# BMS_Segment.net
KiCad netlist of a schematic drawn in EAGLE
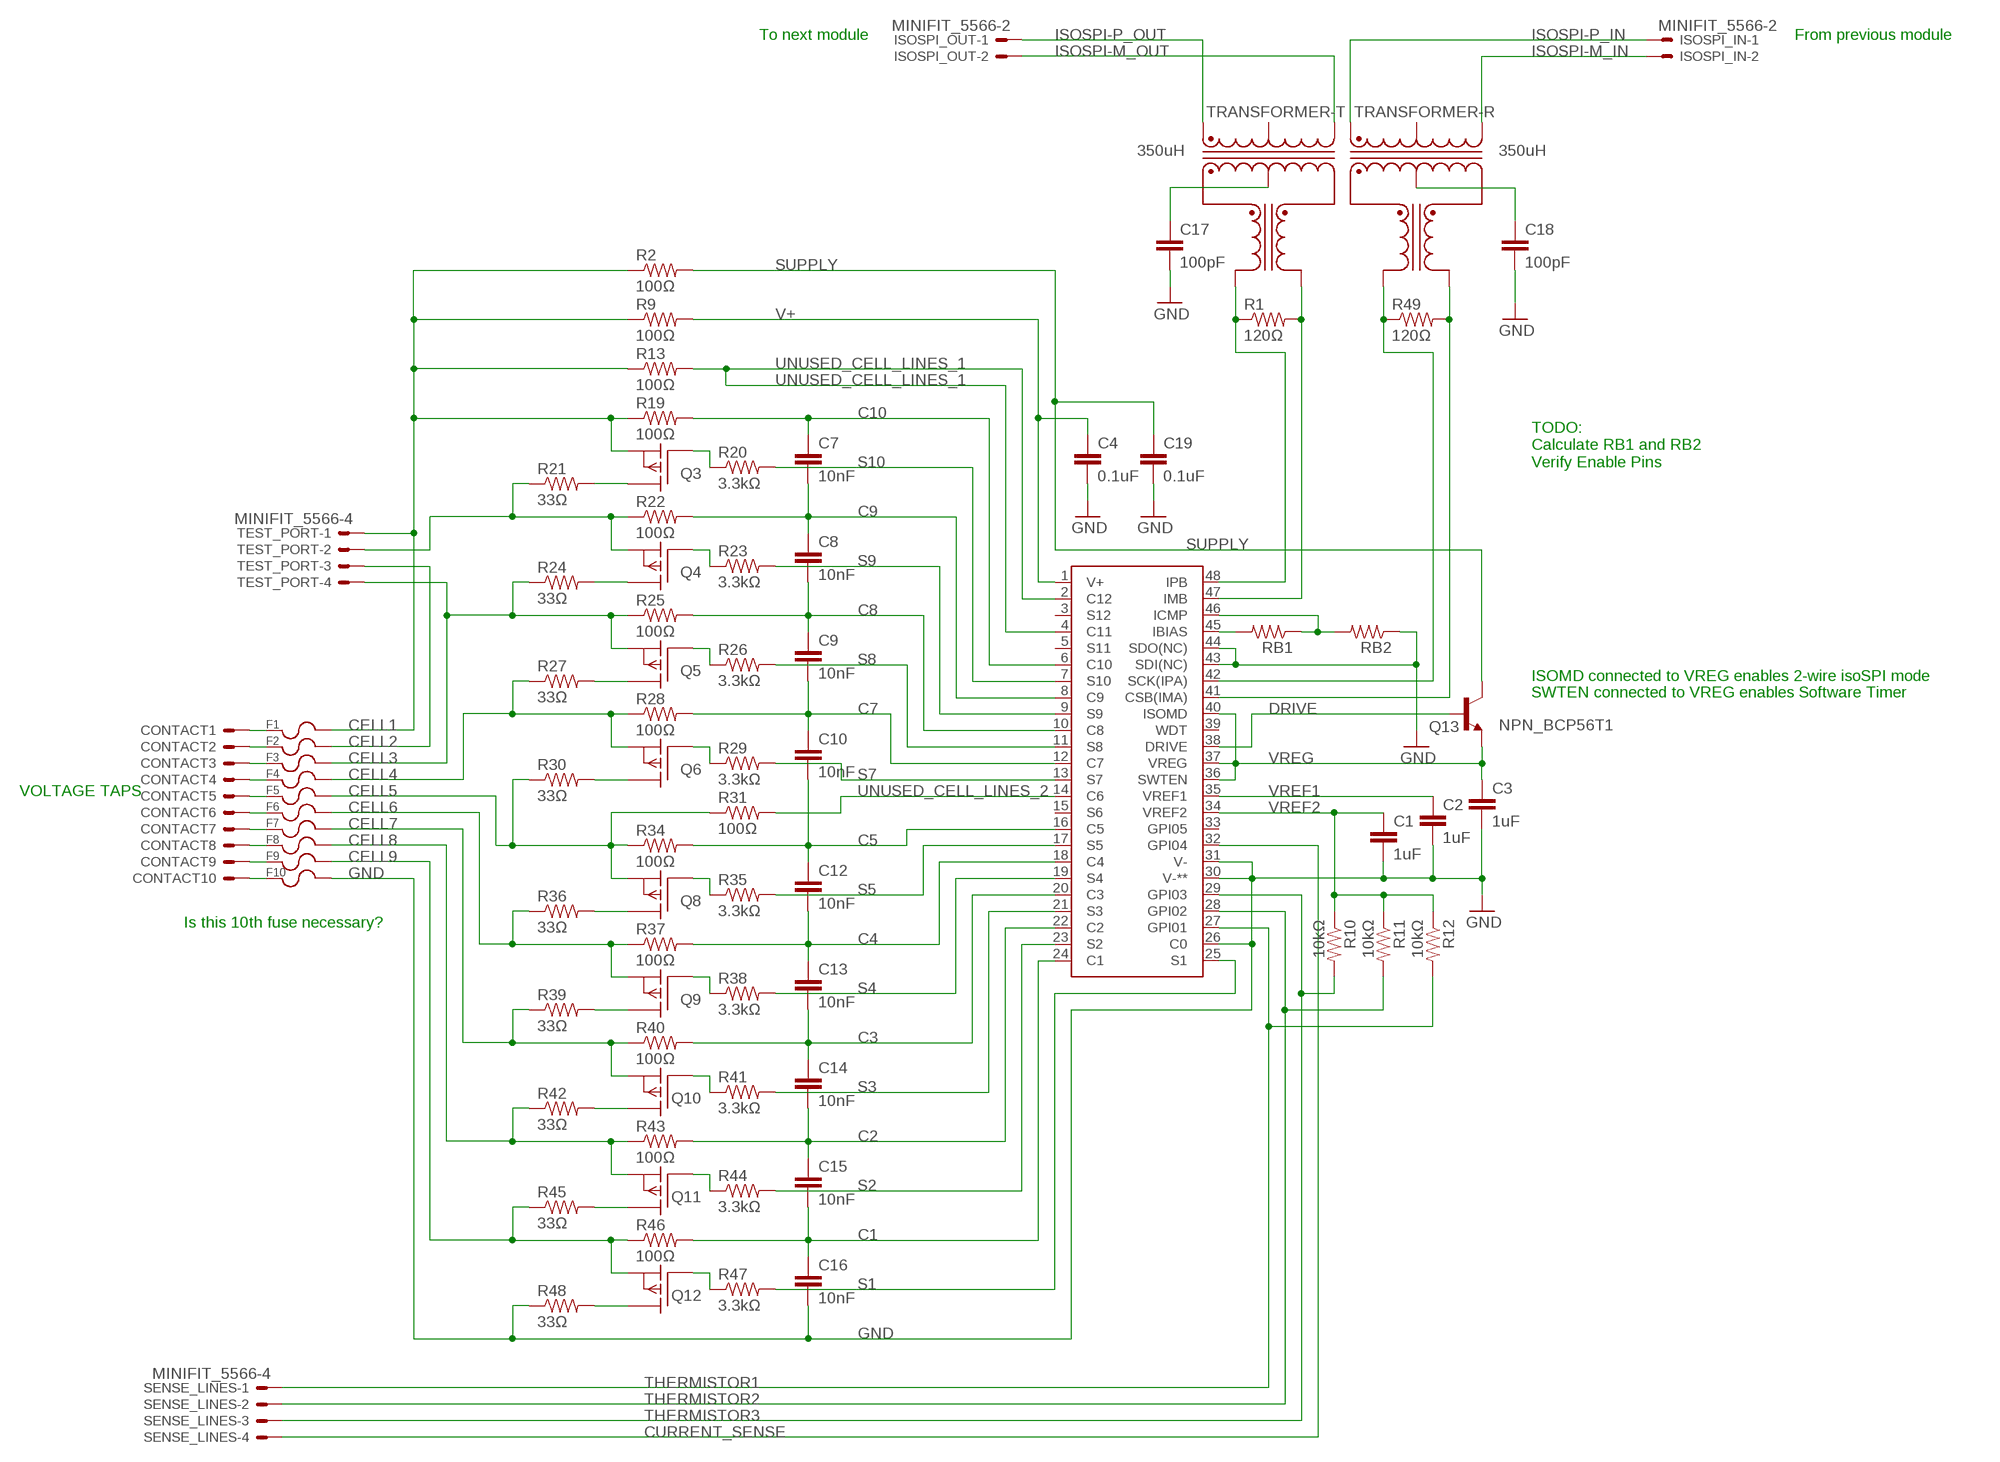
[diagram p0: schematic, sheet 1]

(export (version "E")
  (design (tool "Eeschema 10.0.6"))
  (components
    (comp (ref "C1")
      (value "1uF")
      (footprint "eagle-import:0805")
      (libsource (lib "eagle-import") (part "CAP0805"))
    )
    (comp (ref "C2")
      (value "1uF")
      (footprint "eagle-import:0805")
      (libsource (lib "eagle-import") (part "CAP0805"))
    )
    (comp (ref "C3")
      (value "1uF")
      (footprint "eagle-import:0805")
      (libsource (lib "eagle-import") (part "CAP0805"))
    )
    (comp (ref "C4")
      (value "0.1uF")
      (footprint "eagle-import:0805")
      (libsource (lib "eagle-import") (part "CAP0805"))
    )
    (comp (ref "C7")
      (value "10nF")
      (footprint "eagle-import:0805")
      (libsource (lib "eagle-import") (part "CAP0805"))
    )
    (comp (ref "C8")
      (value "10nF")
      (footprint "eagle-import:0805")
      (libsource (lib "eagle-import") (part "CAP0805"))
    )
    (comp (ref "C9")
      (value "10nF")
      (footprint "eagle-import:0805")
      (libsource (lib "eagle-import") (part "CAP0805"))
    )
    (comp (ref "C10")
      (value "10nF")
      (footprint "eagle-import:0805")
      (libsource (lib "eagle-import") (part "CAP0805"))
    )
    (comp (ref "C12")
      (value "10nF")
      (footprint "eagle-import:0805")
      (libsource (lib "eagle-import") (part "CAP0805"))
    )
    (comp (ref "C13")
      (value "10nF")
      (footprint "eagle-import:0805")
      (libsource (lib "eagle-import") (part "CAP0805"))
    )
    (comp (ref "C14")
      (value "10nF")
      (footprint "eagle-import:0805")
      (libsource (lib "eagle-import") (part "CAP0805"))
    )
    (comp (ref "C15")
      (value "10nF")
      (footprint "eagle-import:0805")
      (libsource (lib "eagle-import") (part "CAP0805"))
    )
    (comp (ref "C16")
      (value "10nF")
      (footprint "eagle-import:0805")
      (libsource (lib "eagle-import") (part "CAP0805"))
    )
    (comp (ref "C17")
      (value "100pF")
      (footprint "eagle-import:0805")
      (libsource (lib "eagle-import") (part "CAP0805"))
    )
    (comp (ref "C18")
      (value "100pF")
      (footprint "eagle-import:0805")
      (libsource (lib "eagle-import") (part "CAP0805"))
    )
    (comp (ref "C19")
      (value "0.1uF")
      (footprint "eagle-import:0805")
      (libsource (lib "eagle-import") (part "CAP0805"))
    )
    (comp (ref "CONTACT1")
      (value "SPRING_CONTACT")
      (footprint "eagle-import:S1791-42R")
      (libsource (lib "eagle-import") (part "SPRING_CONTACT"))
    )
    (comp (ref "CONTACT2")
      (value "SPRING_CONTACT")
      (footprint "eagle-import:S1791-42R")
      (libsource (lib "eagle-import") (part "SPRING_CONTACT"))
    )
    (comp (ref "CONTACT3")
      (value "SPRING_CONTACT")
      (footprint "eagle-import:S1791-42R")
      (libsource (lib "eagle-import") (part "SPRING_CONTACT"))
    )
    (comp (ref "CONTACT4")
      (value "SPRING_CONTACT")
      (footprint "eagle-import:S1791-42R")
      (libsource (lib "eagle-import") (part "SPRING_CONTACT"))
    )
    (comp (ref "CONTACT5")
      (value "SPRING_CONTACT")
      (footprint "eagle-import:S1791-42R")
      (libsource (lib "eagle-import") (part "SPRING_CONTACT"))
    )
    (comp (ref "CONTACT6")
      (value "SPRING_CONTACT")
      (footprint "eagle-import:S1791-42R")
      (libsource (lib "eagle-import") (part "SPRING_CONTACT"))
    )
    (comp (ref "CONTACT7")
      (value "SPRING_CONTACT")
      (footprint "eagle-import:S1791-42R")
      (libsource (lib "eagle-import") (part "SPRING_CONTACT"))
    )
    (comp (ref "CONTACT8")
      (value "SPRING_CONTACT")
      (footprint "eagle-import:S1791-42R")
      (libsource (lib "eagle-import") (part "SPRING_CONTACT"))
    )
    (comp (ref "CONTACT9")
      (value "SPRING_CONTACT")
      (footprint "eagle-import:S1791-42R")
      (libsource (lib "eagle-import") (part "SPRING_CONTACT"))
    )
    (comp (ref "CONTACT10")
      (value "SPRING_CONTACT")
      (footprint "eagle-import:S1791-42R")
      (libsource (lib "eagle-import") (part "SPRING_CONTACT"))
    )
    (comp (ref "F1")
      (value "0751.0110_FUSE_CLIP")
      (footprint "eagle-import:0751.0110")
      (libsource (lib "eagle-import") (part "0751.0110_FUSE_CLIP"))
    )
    (comp (ref "F2")
      (value "0751.0110_FUSE_CLIP")
      (footprint "eagle-import:0751.0110")
      (libsource (lib "eagle-import") (part "0751.0110_FUSE_CLIP"))
    )
    (comp (ref "F3")
      (value "0751.0110_FUSE_CLIP")
      (footprint "eagle-import:0751.0110")
      (libsource (lib "eagle-import") (part "0751.0110_FUSE_CLIP"))
    )
    (comp (ref "F4")
      (value "0751.0110_FUSE_CLIP")
      (footprint "eagle-import:0751.0110")
      (libsource (lib "eagle-import") (part "0751.0110_FUSE_CLIP"))
    )
    (comp (ref "F5")
      (value "0751.0110_FUSE_CLIP")
      (footprint "eagle-import:0751.0110")
      (libsource (lib "eagle-import") (part "0751.0110_FUSE_CLIP"))
    )
    (comp (ref "F6")
      (value "0751.0110_FUSE_CLIP")
      (footprint "eagle-import:0751.0110")
      (libsource (lib "eagle-import") (part "0751.0110_FUSE_CLIP"))
    )
    (comp (ref "F7")
      (value "0751.0110_FUSE_CLIP")
      (footprint "eagle-import:0751.0110")
      (libsource (lib "eagle-import") (part "0751.0110_FUSE_CLIP"))
    )
    (comp (ref "F8")
      (value "0751.0110_FUSE_CLIP")
      (footprint "eagle-import:0751.0110")
      (libsource (lib "eagle-import") (part "0751.0110_FUSE_CLIP"))
    )
    (comp (ref "F9")
      (value "0751.0110_FUSE_CLIP")
      (footprint "eagle-import:0751.0110")
      (libsource (lib "eagle-import") (part "0751.0110_FUSE_CLIP"))
    )
    (comp (ref "F10")
      (value "0751.0110_FUSE_CLIP")
      (footprint "eagle-import:0751.0110")
      (libsource (lib "eagle-import") (part "0751.0110_FUSE_CLIP"))
    )
    (comp (ref "ISOSPI_IN")
      (value "MINIFIT_5566-2")
      (footprint "eagle-import:MINIFIT_5566-2")
      (libsource (lib "eagle-import") (part "MINIFIT_5566-2"))
    )
    (comp (ref "ISOSPI_OUT")
      (value "MINIFIT_5566-2")
      (footprint "eagle-import:MINIFIT_5566-2")
      (libsource (lib "eagle-import") (part "MINIFIT_5566-2"))
    )
    (comp (ref "Q3")
      (value "P-CHANNEL_MOSFET_DMP3099L-7")
      (footprint "eagle-import:SOT23")
      (libsource (lib "eagle-import") (part "P-CHANNEL_MOSFET_DMP3099L-7"))
    )
    (comp (ref "Q4")
      (value "P-CHANNEL_MOSFET_DMP3099L-7")
      (footprint "eagle-import:SOT23")
      (libsource (lib "eagle-import") (part "P-CHANNEL_MOSFET_DMP3099L-7"))
    )
    (comp (ref "Q5")
      (value "P-CHANNEL_MOSFET_DMP3099L-7")
      (footprint "eagle-import:SOT23")
      (libsource (lib "eagle-import") (part "P-CHANNEL_MOSFET_DMP3099L-7"))
    )
    (comp (ref "Q6")
      (value "P-CHANNEL_MOSFET_DMP3099L-7")
      (footprint "eagle-import:SOT23")
      (libsource (lib "eagle-import") (part "P-CHANNEL_MOSFET_DMP3099L-7"))
    )
    (comp (ref "Q8")
      (value "P-CHANNEL_MOSFET_DMP3099L-7")
      (footprint "eagle-import:SOT23")
      (libsource (lib "eagle-import") (part "P-CHANNEL_MOSFET_DMP3099L-7"))
    )
    (comp (ref "Q9")
      (value "P-CHANNEL_MOSFET_DMP3099L-7")
      (footprint "eagle-import:SOT23")
      (libsource (lib "eagle-import") (part "P-CHANNEL_MOSFET_DMP3099L-7"))
    )
    (comp (ref "Q10")
      (value "P-CHANNEL_MOSFET_DMP3099L-7")
      (footprint "eagle-import:SOT23")
      (libsource (lib "eagle-import") (part "P-CHANNEL_MOSFET_DMP3099L-7"))
    )
    (comp (ref "Q11")
      (value "P-CHANNEL_MOSFET_DMP3099L-7")
      (footprint "eagle-import:SOT23")
      (libsource (lib "eagle-import") (part "P-CHANNEL_MOSFET_DMP3099L-7"))
    )
    (comp (ref "Q12")
      (value "P-CHANNEL_MOSFET_DMP3099L-7")
      (footprint "eagle-import:SOT23")
      (libsource (lib "eagle-import") (part "P-CHANNEL_MOSFET_DMP3099L-7"))
    )
    (comp (ref "Q13")
      (value "NPN_BCP56T1")
      (footprint "eagle-import:SOT223")
      (libsource (lib "eagle-import") (part "NPN_BCP56T1"))
    )
    (comp (ref "R1")
      (value "120Ω")
      (footprint "eagle-import:0805")
      (libsource (lib "eagle-import") (part "RESISTOR0805-RES"))
    )
    (comp (ref "R2")
      (value "100Ω")
      (footprint "eagle-import:0805")
      (libsource (lib "eagle-import") (part "RESISTOR0805-RES"))
    )
    (comp (ref "R9")
      (value "100Ω")
      (footprint "eagle-import:0805")
      (libsource (lib "eagle-import") (part "RESISTOR0805-RES"))
    )
    (comp (ref "R10")
      (value "10kΩ")
      (footprint "eagle-import:0805")
      (libsource (lib "eagle-import") (part "RESISTOR0805-RES"))
    )
    (comp (ref "R11")
      (value "10kΩ")
      (footprint "eagle-import:0805")
      (libsource (lib "eagle-import") (part "RESISTOR0805-RES"))
    )
    (comp (ref "R12")
      (value "10kΩ")
      (footprint "eagle-import:0805")
      (libsource (lib "eagle-import") (part "RESISTOR0805-RES"))
    )
    (comp (ref "R13")
      (value "100Ω")
      (footprint "eagle-import:0805")
      (libsource (lib "eagle-import") (part "RESISTOR0805-RES"))
    )
    (comp (ref "R19")
      (value "100Ω")
      (footprint "eagle-import:0805")
      (libsource (lib "eagle-import") (part "RESISTOR0805-RES"))
    )
    (comp (ref "R20")
      (value "3.3kΩ")
      (footprint "eagle-import:0805")
      (libsource (lib "eagle-import") (part "RESISTOR0805-RES"))
    )
    (comp (ref "R21")
      (value "33Ω")
      (footprint "eagle-import:R2512")
      (libsource (lib "eagle-import") (part "RESISTOR2512"))
    )
    (comp (ref "R22")
      (value "100Ω")
      (footprint "eagle-import:0805")
      (libsource (lib "eagle-import") (part "RESISTOR0805-RES"))
    )
    (comp (ref "R23")
      (value "3.3kΩ")
      (footprint "eagle-import:0805")
      (libsource (lib "eagle-import") (part "RESISTOR0805-RES"))
    )
    (comp (ref "R24")
      (value "33Ω")
      (footprint "eagle-import:R2512")
      (libsource (lib "eagle-import") (part "RESISTOR2512"))
    )
    (comp (ref "R25")
      (value "100Ω")
      (footprint "eagle-import:0805")
      (libsource (lib "eagle-import") (part "RESISTOR0805-RES"))
    )
    (comp (ref "R26")
      (value "3.3kΩ")
      (footprint "eagle-import:0805")
      (libsource (lib "eagle-import") (part "RESISTOR0805-RES"))
    )
    (comp (ref "R27")
      (value "33Ω")
      (footprint "eagle-import:R2512")
      (libsource (lib "eagle-import") (part "RESISTOR2512"))
    )
    (comp (ref "R28")
      (value "100Ω")
      (footprint "eagle-import:0805")
      (libsource (lib "eagle-import") (part "RESISTOR0805-RES"))
    )
    (comp (ref "R29")
      (value "3.3kΩ")
      (footprint "eagle-import:0805")
      (libsource (lib "eagle-import") (part "RESISTOR0805-RES"))
    )
    (comp (ref "R30")
      (value "33Ω")
      (footprint "eagle-import:R2512")
      (libsource (lib "eagle-import") (part "RESISTOR2512"))
    )
    (comp (ref "R31")
      (value "100Ω")
      (footprint "eagle-import:0805")
      (libsource (lib "eagle-import") (part "RESISTOR0805-RES"))
    )
    (comp (ref "R34")
      (value "100Ω")
      (footprint "eagle-import:0805")
      (libsource (lib "eagle-import") (part "RESISTOR0805-RES"))
    )
    (comp (ref "R35")
      (value "3.3kΩ")
      (footprint "eagle-import:0805")
      (libsource (lib "eagle-import") (part "RESISTOR0805-RES"))
    )
    (comp (ref "R36")
      (value "33Ω")
      (footprint "eagle-import:R2512")
      (libsource (lib "eagle-import") (part "RESISTOR2512"))
    )
    (comp (ref "R37")
      (value "100Ω")
      (footprint "eagle-import:0805")
      (libsource (lib "eagle-import") (part "RESISTOR0805-RES"))
    )
    (comp (ref "R38")
      (value "3.3kΩ")
      (footprint "eagle-import:0805")
      (libsource (lib "eagle-import") (part "RESISTOR0805-RES"))
    )
    (comp (ref "R39")
      (value "33Ω")
      (footprint "eagle-import:R2512")
      (libsource (lib "eagle-import") (part "RESISTOR2512"))
    )
    (comp (ref "R40")
      (value "100Ω")
      (footprint "eagle-import:0805")
      (libsource (lib "eagle-import") (part "RESISTOR0805-RES"))
    )
    (comp (ref "R41")
      (value "3.3kΩ")
      (footprint "eagle-import:0805")
      (libsource (lib "eagle-import") (part "RESISTOR0805-RES"))
    )
    (comp (ref "R42")
      (value "33Ω")
      (footprint "eagle-import:R2512")
      (libsource (lib "eagle-import") (part "RESISTOR2512"))
    )
    (comp (ref "R43")
      (value "100Ω")
      (footprint "eagle-import:0805")
      (libsource (lib "eagle-import") (part "RESISTOR0805-RES"))
    )
    (comp (ref "R44")
      (value "3.3kΩ")
      (footprint "eagle-import:0805")
      (libsource (lib "eagle-import") (part "RESISTOR0805-RES"))
    )
    (comp (ref "R45")
      (value "33Ω")
      (footprint "eagle-import:R2512")
      (libsource (lib "eagle-import") (part "RESISTOR2512"))
    )
    (comp (ref "R46")
      (value "100Ω")
      (footprint "eagle-import:0805")
      (libsource (lib "eagle-import") (part "RESISTOR0805-RES"))
    )
    (comp (ref "R47")
      (value "3.3kΩ")
      (footprint "eagle-import:0805")
      (libsource (lib "eagle-import") (part "RESISTOR0805-RES"))
    )
    (comp (ref "R48")
      (value "33Ω")
      (footprint "eagle-import:R2512")
      (libsource (lib "eagle-import") (part "RESISTOR2512"))
    )
    (comp (ref "R49")
      (value "120Ω")
      (footprint "eagle-import:0805")
      (libsource (lib "eagle-import") (part "RESISTOR0805-RES"))
    )
    (comp (ref "RB1")
      (value "RESISTOR0805-RES")
      (footprint "eagle-import:0805")
      (libsource (lib "eagle-import") (part "RESISTOR0805-RES"))
    )
    (comp (ref "RB2")
      (value "RESISTOR0805-RES")
      (footprint "eagle-import:0805")
      (libsource (lib "eagle-import") (part "RESISTOR0805-RES"))
    )
    (comp (ref "SENSE_LINES")
      (value "MINIFIT_5566-4")
      (footprint "eagle-import:MINIFIT_5566-4")
      (libsource (lib "eagle-import") (part "MINIFIT_5566-4"))
    )
    (comp (ref "TEST_PORT")
      (value "MINIFIT_5566-4")
      (footprint "eagle-import:MINIFIT_5566-4")
      (libsource (lib "eagle-import") (part "MINIFIT_5566-4"))
    )
    (comp (ref "TRANSFORMER-")
      (value "350uH")
      (footprint "eagle-import:749010013")
      (libsource (lib "eagle-import") (part "TRANSFORMER_749010013"))
    )
    (comp (ref "U$2")
      (value "LTC6804-1")
      (footprint "eagle-import:LTC6804")
      (libsource (lib "eagle-import") (part "LTC6804-1"))
    )
  )
  (nets
    (net (code "1") (name "/C1") (class "Default")
      (node (ref "C15") (pin "2") (pinfunction "2_2") (pintype "passive"))
      (node (ref "C16") (pin "1") (pinfunction "1_1") (pintype "passive"))
      (node (ref "R46") (pin "2") (pinfunction "2_2") (pintype "passive"))
      (node (ref "U$2") (pin "24") (pinfunction "C1_24") (pintype "bidirectional"))
    )
    (net (code "2") (name "/C2") (class "Default")
      (node (ref "C14") (pin "2") (pinfunction "2_2") (pintype "passive"))
      (node (ref "C15") (pin "1") (pinfunction "1_1") (pintype "passive"))
      (node (ref "R43") (pin "2") (pinfunction "2_2") (pintype "passive"))
      (node (ref "U$2") (pin "22") (pinfunction "C2_22") (pintype "bidirectional"))
    )
    (net (code "3") (name "/C3") (class "Default")
      (node (ref "C13") (pin "2") (pinfunction "2_2") (pintype "passive"))
      (node (ref "C14") (pin "1") (pinfunction "1_1") (pintype "passive"))
      (node (ref "R40") (pin "2") (pinfunction "2_2") (pintype "passive"))
      (node (ref "U$2") (pin "20") (pinfunction "C3_20") (pintype "bidirectional"))
    )
    (net (code "4") (name "/C4") (class "Default")
      (node (ref "C12") (pin "2") (pinfunction "2_2") (pintype "passive"))
      (node (ref "C13") (pin "1") (pinfunction "1_1") (pintype "passive"))
      (node (ref "R37") (pin "2") (pinfunction "2_2") (pintype "passive"))
      (node (ref "U$2") (pin "18") (pinfunction "C4_18") (pintype "bidirectional"))
    )
    (net (code "5") (name "/C5") (class "Default")
      (node (ref "C10") (pin "2") (pinfunction "2_2") (pintype "passive"))
      (node (ref "C12") (pin "1") (pinfunction "1_1") (pintype "passive"))
      (node (ref "R34") (pin "2") (pinfunction "2_2") (pintype "passive"))
      (node (ref "U$2") (pin "16") (pinfunction "C5_16") (pintype "bidirectional"))
    )
    (net (code "6") (name "/C7") (class "Default")
      (node (ref "C10") (pin "1") (pinfunction "1_1") (pintype "passive"))
      (node (ref "C9") (pin "2") (pinfunction "2_2") (pintype "passive"))
      (node (ref "R28") (pin "2") (pinfunction "2_2") (pintype "passive"))
      (node (ref "U$2") (pin "12") (pinfunction "C7_12") (pintype "bidirectional"))
    )
    (net (code "7") (name "/C8") (class "Default")
      (node (ref "C8") (pin "2") (pinfunction "2_2") (pintype "passive"))
      (node (ref "C9") (pin "1") (pinfunction "1_1") (pintype "passive"))
      (node (ref "R25") (pin "2") (pinfunction "2_2") (pintype "passive"))
      (node (ref "U$2") (pin "10") (pinfunction "C8_10") (pintype "bidirectional"))
    )
    (net (code "8") (name "/C9") (class "Default")
      (node (ref "C7") (pin "2") (pinfunction "2_2") (pintype "passive"))
      (node (ref "C8") (pin "1") (pinfunction "1_1") (pintype "passive"))
      (node (ref "R22") (pin "2") (pinfunction "2_2") (pintype "passive"))
      (node (ref "U$2") (pin "8") (pinfunction "C9_8") (pintype "bidirectional"))
    )
    (net (code "9") (name "/C10") (class "Default")
      (node (ref "C7") (pin "1") (pinfunction "1_1") (pintype "passive"))
      (node (ref "R19") (pin "2") (pinfunction "2_2") (pintype "passive"))
      (node (ref "U$2") (pin "6") (pinfunction "C10_6") (pintype "bidirectional"))
    )
    (net (code "10") (name "/CELL1") (class "Default")
      (node (ref "F1") (pin "R1") (pinfunction "2_R1") (pintype "bidirectional"))
      (node (ref "F1") (pin "R2") (pinfunction "2_R2") (pintype "bidirectional"))
      (node (ref "Q3") (pin "2") (pinfunction "S_2") (pintype "passive"))
      (node (ref "R13") (pin "1") (pinfunction "1_1") (pintype "passive"))
      (node (ref "R19") (pin "1") (pinfunction "1_1") (pintype "passive"))
      (node (ref "R2") (pin "1") (pinfunction "1_1") (pintype "passive"))
      (node (ref "R9") (pin "1") (pinfunction "1_1") (pintype "passive"))
      (node (ref "TEST_PORT") (pin "1") (pinfunction "S_1") (pintype "passive"))
    )
    (net (code "11") (name "/CELL2") (class "Default")
      (node (ref "F2") (pin "R1") (pinfunction "2_R1") (pintype "bidirectional"))
      (node (ref "F2") (pin "R2") (pinfunction "2_R2") (pintype "bidirectional"))
      (node (ref "Q4") (pin "2") (pinfunction "S_2") (pintype "passive"))
      (node (ref "R21") (pin "1") (pinfunction "1_1") (pintype "passive"))
      (node (ref "R22") (pin "1") (pinfunction "1_1") (pintype "passive"))
      (node (ref "TEST_PORT") (pin "2") (pinfunction "S_2") (pintype "passive"))
      (node (ref "TEST_PORT") (pin "3") (pinfunction "S_3") (pintype "passive"))
    )
    (net (code "12") (name "/CELL3") (class "Default")
      (node (ref "F3") (pin "R1") (pinfunction "2_R1") (pintype "bidirectional"))
      (node (ref "F3") (pin "R2") (pinfunction "2_R2") (pintype "bidirectional"))
      (node (ref "Q5") (pin "2") (pinfunction "S_2") (pintype "passive"))
      (node (ref "R24") (pin "1") (pinfunction "1_1") (pintype "passive"))
      (node (ref "R25") (pin "1") (pinfunction "1_1") (pintype "passive"))
      (node (ref "TEST_PORT") (pin "4") (pinfunction "S_4") (pintype "passive"))
    )
    (net (code "13") (name "/CELL4") (class "Default")
      (node (ref "F4") (pin "R1") (pinfunction "2_R1") (pintype "bidirectional"))
      (node (ref "F4") (pin "R2") (pinfunction "2_R2") (pintype "bidirectional"))
      (node (ref "Q6") (pin "2") (pinfunction "S_2") (pintype "passive"))
      (node (ref "R27") (pin "1") (pinfunction "1_1") (pintype "passive"))
      (node (ref "R28") (pin "1") (pinfunction "1_1") (pintype "passive"))
    )
    (net (code "14") (name "/CELL5") (class "Default")
      (node (ref "F5") (pin "R1") (pinfunction "2_R1") (pintype "bidirectional"))
      (node (ref "F5") (pin "R2") (pinfunction "2_R2") (pintype "bidirectional"))
      (node (ref "Q8") (pin "2") (pinfunction "S_2") (pintype "passive"))
      (node (ref "R30") (pin "1") (pinfunction "1_1") (pintype "passive"))
      (node (ref "R31") (pin "1") (pinfunction "1_1") (pintype "passive"))
      (node (ref "R34") (pin "1") (pinfunction "1_1") (pintype "passive"))
    )
    (net (code "15") (name "/CELL6") (class "Default")
      (node (ref "F6") (pin "R1") (pinfunction "2_R1") (pintype "bidirectional"))
      (node (ref "F6") (pin "R2") (pinfunction "2_R2") (pintype "bidirectional"))
      (node (ref "Q9") (pin "2") (pinfunction "S_2") (pintype "passive"))
      (node (ref "R36") (pin "1") (pinfunction "1_1") (pintype "passive"))
      (node (ref "R37") (pin "1") (pinfunction "1_1") (pintype "passive"))
    )
    (net (code "16") (name "/CELL7") (class "Default")
      (node (ref "F7") (pin "R1") (pinfunction "2_R1") (pintype "bidirectional"))
      (node (ref "F7") (pin "R2") (pinfunction "2_R2") (pintype "bidirectional"))
      (node (ref "Q10") (pin "2") (pinfunction "S_2") (pintype "passive"))
      (node (ref "R39") (pin "1") (pinfunction "1_1") (pintype "passive"))
      (node (ref "R40") (pin "1") (pinfunction "1_1") (pintype "passive"))
    )
    (net (code "17") (name "/CELL8") (class "Default")
      (node (ref "F8") (pin "R1") (pinfunction "2_R1") (pintype "bidirectional"))
      (node (ref "F8") (pin "R2") (pinfunction "2_R2") (pintype "bidirectional"))
      (node (ref "Q11") (pin "2") (pinfunction "S_2") (pintype "passive"))
      (node (ref "R42") (pin "1") (pinfunction "1_1") (pintype "passive"))
      (node (ref "R43") (pin "1") (pinfunction "1_1") (pintype "passive"))
    )
    (net (code "18") (name "/CELL9") (class "Default")
      (node (ref "F9") (pin "R1") (pinfunction "2_R1") (pintype "bidirectional"))
      (node (ref "F9") (pin "R2") (pinfunction "2_R2") (pintype "bidirectional"))
      (node (ref "Q12") (pin "2") (pinfunction "S_2") (pintype "passive"))
      (node (ref "R45") (pin "1") (pinfunction "1_1") (pintype "passive"))
      (node (ref "R46") (pin "1") (pinfunction "1_1") (pintype "passive"))
    )
    (net (code "19") (name "/CURRENT_SENSE") (class "Default")
      (node (ref "SENSE_LINES") (pin "4") (pinfunction "S_4") (pintype "passive"))
      (node (ref "U$2") (pin "32") (pinfunction "GPI04_32") (pintype "bidirectional"))
    )
    (net (code "20") (name "/DRIVE") (class "Default")
      (node (ref "Q13") (pin "1") (pinfunction "BASE_1") (pintype "passive"))
      (node (ref "U$2") (pin "38") (pinfunction "DRIVE_38") (pintype "bidirectional"))
    )
    (net (code "21") (name "/ISOSPI-M_IN") (class "Default")
      (node (ref "ISOSPI_IN") (pin "2") (pinfunction "S_2") (pintype "passive"))
      (node (ref "TRANSFORMER-") (pin "8") (pinfunction "D-_8") (pintype "passive"))
    )
    (net (code "22") (name "/ISOSPI-M_OUT") (class "Default")
      (node (ref "ISOSPI_OUT") (pin "2") (pinfunction "S_2") (pintype "passive"))
      (node (ref "TRANSFORMER-") (pin "3") (pinfunction "D-_3") (pintype "passive"))
    )
    (net (code "23") (name "/ISOSPI-P_IN") (class "Default")
      (node (ref "ISOSPI_IN") (pin "1") (pinfunction "S_1") (pintype "passive"))
      (node (ref "TRANSFORMER-") (pin "6") (pinfunction "D+_6") (pintype "passive"))
    )
    (net (code "24") (name "/ISOSPI-P_OUT") (class "Default")
      (node (ref "ISOSPI_OUT") (pin "1") (pinfunction "S_1") (pintype "passive"))
      (node (ref "TRANSFORMER-") (pin "1") (pinfunction "D+_1") (pintype "passive"))
    )
    (net (code "25") (name "/S1") (class "Default")
      (node (ref "R47") (pin "2") (pinfunction "2_2") (pintype "passive"))
      (node (ref "U$2") (pin "25") (pinfunction "S1_25") (pintype "bidirectional"))
    )
    (net (code "26") (name "/S2") (class "Default")
      (node (ref "R44") (pin "2") (pinfunction "2_2") (pintype "passive"))
      (node (ref "U$2") (pin "23") (pinfunction "S2_23") (pintype "bidirectional"))
    )
    (net (code "27") (name "/S3") (class "Default")
      (node (ref "R41") (pin "2") (pinfunction "2_2") (pintype "passive"))
      (node (ref "U$2") (pin "21") (pinfunction "S3_21") (pintype "bidirectional"))
    )
    (net (code "28") (name "/S4") (class "Default")
      (node (ref "R38") (pin "2") (pinfunction "2_2") (pintype "passive"))
      (node (ref "U$2") (pin "19") (pinfunction "S4_19") (pintype "bidirectional"))
    )
    (net (code "29") (name "/S5") (class "Default")
      (node (ref "R35") (pin "2") (pinfunction "2_2") (pintype "passive"))
      (node (ref "U$2") (pin "17") (pinfunction "S5_17") (pintype "bidirectional"))
    )
    (net (code "30") (name "/S7") (class "Default")
      (node (ref "R29") (pin "2") (pinfunction "2_2") (pintype "passive"))
      (node (ref "U$2") (pin "13") (pinfunction "S7_13") (pintype "bidirectional"))
    )
    (net (code "31") (name "/S8") (class "Default")
      (node (ref "R26") (pin "2") (pinfunction "2_2") (pintype "passive"))
      (node (ref "U$2") (pin "11") (pinfunction "S8_11") (pintype "bidirectional"))
    )
    (net (code "32") (name "/S9") (class "Default")
      (node (ref "R23") (pin "2") (pinfunction "2_2") (pintype "passive"))
      (node (ref "U$2") (pin "9") (pinfunction "S9_9") (pintype "bidirectional"))
    )
    (net (code "33") (name "/S10") (class "Default")
      (node (ref "R20") (pin "2") (pinfunction "2_2") (pintype "passive"))
      (node (ref "U$2") (pin "7") (pinfunction "S10_7") (pintype "bidirectional"))
    )
    (net (code "34") (name "/SUPPLY") (class "Default")
      (node (ref "C19") (pin "1") (pinfunction "1_1") (pintype "passive"))
      (node (ref "Q13") (pin "2") (pinfunction "COLLECTOR_2") (pintype "passive"))
      (node (ref "Q13") (pin "4") (pinfunction "COLLECTOR_4") (pintype "passive"))
      (node (ref "R2") (pin "2") (pinfunction "2_2") (pintype "passive"))
    )
    (net (code "35") (name "/THERMISTOR1") (class "Default")
      (node (ref "R12") (pin "2") (pinfunction "2_2") (pintype "passive"))
      (node (ref "SENSE_LINES") (pin "1") (pinfunction "S_1") (pintype "passive"))
      (node (ref "U$2") (pin "27") (pinfunction "GPI01_27") (pintype "bidirectional"))
    )
    (net (code "36") (name "/THERMISTOR2") (class "Default")
      (node (ref "R11") (pin "2") (pinfunction "2_2") (pintype "passive"))
      (node (ref "SENSE_LINES") (pin "2") (pinfunction "S_2") (pintype "passive"))
      (node (ref "U$2") (pin "28") (pinfunction "GPI02_28") (pintype "bidirectional"))
    )
    (net (code "37") (name "/THERMISTOR3") (class "Default")
      (node (ref "R10") (pin "2") (pinfunction "2_2") (pintype "passive"))
      (node (ref "SENSE_LINES") (pin "3") (pinfunction "S_3") (pintype "passive"))
      (node (ref "U$2") (pin "29") (pinfunction "GPI03_29") (pintype "bidirectional"))
    )
    (net (code "38") (name "/UNUSED_CELL_LINES_1") (class "Default")
      (node (ref "R13") (pin "2") (pinfunction "2_2") (pintype "passive"))
      (node (ref "U$2") (pin "2") (pinfunction "C12_2") (pintype "bidirectional"))
      (node (ref "U$2") (pin "4") (pinfunction "C11_4") (pintype "bidirectional"))
    )
    (net (code "39") (name "/UNUSED_CELL_LINES_2") (class "Default")
      (node (ref "R31") (pin "2") (pinfunction "2_2") (pintype "passive"))
      (node (ref "U$2") (pin "14") (pinfunction "C6_14") (pintype "bidirectional"))
    )
    (net (code "40") (name "/V+") (class "Default")
      (node (ref "C4") (pin "1") (pinfunction "1_1") (pintype "passive"))
      (node (ref "R9") (pin "2") (pinfunction "2_2") (pintype "passive"))
      (node (ref "U$2") (pin "1") (pinfunction "V+_1") (pintype "bidirectional"))
    )
    (net (code "41") (name "/VREF1") (class "Default")
      (node (ref "C2") (pin "1") (pinfunction "1_1") (pintype "passive"))
      (node (ref "U$2") (pin "35") (pinfunction "VREF1_35") (pintype "bidirectional"))
    )
    (net (code "42") (name "/VREF2") (class "Default")
      (node (ref "C1") (pin "1") (pinfunction "1_1") (pintype "passive"))
      (node (ref "R10") (pin "1") (pinfunction "1_1") (pintype "passive"))
      (node (ref "R11") (pin "1") (pinfunction "1_1") (pintype "passive"))
      (node (ref "R12") (pin "1") (pinfunction "1_1") (pintype "passive"))
      (node (ref "U$2") (pin "34") (pinfunction "VREF2_34") (pintype "bidirectional"))
    )
    (net (code "43") (name "/VREG") (class "Default")
      (node (ref "C3") (pin "1") (pinfunction "1_1") (pintype "passive"))
      (node (ref "Q13") (pin "3") (pinfunction "EMITTER_3") (pintype "passive"))
      (node (ref "U$2") (pin "36") (pinfunction "SWTEN_36") (pintype "bidirectional"))
      (node (ref "U$2") (pin "37") (pinfunction "VREG_37") (pintype "bidirectional"))
      (node (ref "U$2") (pin "40") (pinfunction "ISOMD_40") (pintype "bidirectional"))
    )
    (net (code "44") (name "GND") (class "Default")
      (node (ref "C1") (pin "2") (pinfunction "2_2") (pintype "passive"))
      (node (ref "C16") (pin "2") (pinfunction "2_2") (pintype "passive"))
      (node (ref "C17") (pin "2") (pinfunction "2_2") (pintype "passive"))
      (node (ref "C18") (pin "2") (pinfunction "2_2") (pintype "passive"))
      (node (ref "C19") (pin "2") (pinfunction "2_2") (pintype "passive"))
      (node (ref "C2") (pin "2") (pinfunction "2_2") (pintype "passive"))
      (node (ref "C3") (pin "2") (pinfunction "2_2") (pintype "passive"))
      (node (ref "C4") (pin "2") (pinfunction "2_2") (pintype "passive"))
      (node (ref "F10") (pin "R1") (pinfunction "2_R1") (pintype "bidirectional"))
      (node (ref "F10") (pin "R2") (pinfunction "2_R2") (pintype "bidirectional"))
      (node (ref "R48") (pin "1") (pinfunction "1_1") (pintype "passive"))
      (node (ref "RB2") (pin "1") (pinfunction "1_1") (pintype "passive"))
      (node (ref "U$2") (pin "26") (pinfunction "C0_26") (pintype "bidirectional"))
      (node (ref "U$2") (pin "30") (pinfunction "V-**_30") (pintype "bidirectional"))
      (node (ref "U$2") (pin "31") (pinfunction "V-_31") (pintype "bidirectional"))
      (node (ref "U$2") (pin "43") (pinfunction "SDI(NC)_43") (pintype "bidirectional"))
      (node (ref "U$2") (pin "44") (pinfunction "SDO(NC)_44") (pintype "bidirectional"))
    )
    (net (code "45") (name "Net-(CONTACT1-S)") (class "Default")
      (node (ref "CONTACT1") (pin "P$1") (pinfunction "S_P$1") (pintype "passive"))
      (node (ref "F1") (pin "L1") (pinfunction "1_L1") (pintype "bidirectional"))
      (node (ref "F1") (pin "L2") (pinfunction "1_L2") (pintype "bidirectional"))
    )
    (net (code "46") (name "Net-(CONTACT2-S)") (class "Default")
      (node (ref "CONTACT2") (pin "P$1") (pinfunction "S_P$1") (pintype "passive"))
      (node (ref "F2") (pin "L1") (pinfunction "1_L1") (pintype "bidirectional"))
      (node (ref "F2") (pin "L2") (pinfunction "1_L2") (pintype "bidirectional"))
    )
    (net (code "47") (name "Net-(CONTACT3-S)") (class "Default")
      (node (ref "CONTACT3") (pin "P$1") (pinfunction "S_P$1") (pintype "passive"))
      (node (ref "F3") (pin "L1") (pinfunction "1_L1") (pintype "bidirectional"))
      (node (ref "F3") (pin "L2") (pinfunction "1_L2") (pintype "bidirectional"))
    )
    (net (code "48") (name "Net-(CONTACT4-S)") (class "Default")
      (node (ref "CONTACT4") (pin "P$1") (pinfunction "S_P$1") (pintype "passive"))
      (node (ref "F4") (pin "L1") (pinfunction "1_L1") (pintype "bidirectional"))
      (node (ref "F4") (pin "L2") (pinfunction "1_L2") (pintype "bidirectional"))
    )
    (net (code "49") (name "Net-(CONTACT5-S)") (class "Default")
      (node (ref "CONTACT5") (pin "P$1") (pinfunction "S_P$1") (pintype "passive"))
      (node (ref "F5") (pin "L1") (pinfunction "1_L1") (pintype "bidirectional"))
      (node (ref "F5") (pin "L2") (pinfunction "1_L2") (pintype "bidirectional"))
    )
    (net (code "50") (name "Net-(CONTACT6-S)") (class "Default")
      (node (ref "CONTACT6") (pin "P$1") (pinfunction "S_P$1") (pintype "passive"))
      (node (ref "F6") (pin "L1") (pinfunction "1_L1") (pintype "bidirectional"))
      (node (ref "F6") (pin "L2") (pinfunction "1_L2") (pintype "bidirectional"))
    )
    (net (code "51") (name "Net-(CONTACT7-S)") (class "Default")
      (node (ref "CONTACT7") (pin "P$1") (pinfunction "S_P$1") (pintype "passive"))
      (node (ref "F7") (pin "L1") (pinfunction "1_L1") (pintype "bidirectional"))
      (node (ref "F7") (pin "L2") (pinfunction "1_L2") (pintype "bidirectional"))
    )
    (net (code "52") (name "Net-(CONTACT8-S)") (class "Default")
      (node (ref "CONTACT8") (pin "P$1") (pinfunction "S_P$1") (pintype "passive"))
      (node (ref "F8") (pin "L1") (pinfunction "1_L1") (pintype "bidirectional"))
      (node (ref "F8") (pin "L2") (pinfunction "1_L2") (pintype "bidirectional"))
    )
    (net (code "53") (name "Net-(CONTACT9-S)") (class "Default")
      (node (ref "CONTACT9") (pin "P$1") (pinfunction "S_P$1") (pintype "passive"))
      (node (ref "F9") (pin "L1") (pinfunction "1_L1") (pintype "bidirectional"))
      (node (ref "F9") (pin "L2") (pinfunction "1_L2") (pintype "bidirectional"))
    )
    (net (code "54") (name "Net-(CONTACT10-S)") (class "Default")
      (node (ref "CONTACT10") (pin "P$1") (pinfunction "S_P$1") (pintype "passive"))
      (node (ref "F10") (pin "L1") (pinfunction "1_L1") (pintype "bidirectional"))
      (node (ref "F10") (pin "L2") (pinfunction "1_L2") (pintype "bidirectional"))
    )
    (net (code "55") (name "Net-(Q3-D)") (class "Default")
      (node (ref "Q3") (pin "3") (pinfunction "D_3") (pintype "passive"))
      (node (ref "R21") (pin "2") (pinfunction "2_2") (pintype "passive"))
    )
    (net (code "56") (name "Net-(Q3-G)") (class "Default")
      (node (ref "Q3") (pin "1") (pinfunction "G_1") (pintype "passive"))
      (node (ref "R20") (pin "1") (pinfunction "1_1") (pintype "passive"))
    )
    (net (code "57") (name "Net-(Q4-D)") (class "Default")
      (node (ref "Q4") (pin "3") (pinfunction "D_3") (pintype "passive"))
      (node (ref "R24") (pin "2") (pinfunction "2_2") (pintype "passive"))
    )
    (net (code "58") (name "Net-(Q4-G)") (class "Default")
      (node (ref "Q4") (pin "1") (pinfunction "G_1") (pintype "passive"))
      (node (ref "R23") (pin "1") (pinfunction "1_1") (pintype "passive"))
    )
    (net (code "59") (name "Net-(Q5-D)") (class "Default")
      (node (ref "Q5") (pin "3") (pinfunction "D_3") (pintype "passive"))
      (node (ref "R27") (pin "2") (pinfunction "2_2") (pintype "passive"))
    )
    (net (code "60") (name "Net-(Q5-G)") (class "Default")
      (node (ref "Q5") (pin "1") (pinfunction "G_1") (pintype "passive"))
      (node (ref "R26") (pin "1") (pinfunction "1_1") (pintype "passive"))
    )
    (net (code "61") (name "Net-(Q6-D)") (class "Default")
      (node (ref "Q6") (pin "3") (pinfunction "D_3") (pintype "passive"))
      (node (ref "R30") (pin "2") (pinfunction "2_2") (pintype "passive"))
    )
    (net (code "62") (name "Net-(Q6-G)") (class "Default")
      (node (ref "Q6") (pin "1") (pinfunction "G_1") (pintype "passive"))
      (node (ref "R29") (pin "1") (pinfunction "1_1") (pintype "passive"))
    )
    (net (code "63") (name "Net-(Q8-D)") (class "Default")
      (node (ref "Q8") (pin "3") (pinfunction "D_3") (pintype "passive"))
      (node (ref "R36") (pin "2") (pinfunction "2_2") (pintype "passive"))
    )
    (net (code "64") (name "Net-(Q8-G)") (class "Default")
      (node (ref "Q8") (pin "1") (pinfunction "G_1") (pintype "passive"))
      (node (ref "R35") (pin "1") (pinfunction "1_1") (pintype "passive"))
    )
    (net (code "65") (name "Net-(Q9-D)") (class "Default")
      (node (ref "Q9") (pin "3") (pinfunction "D_3") (pintype "passive"))
      (node (ref "R39") (pin "2") (pinfunction "2_2") (pintype "passive"))
    )
    (net (code "66") (name "Net-(Q9-G)") (class "Default")
      (node (ref "Q9") (pin "1") (pinfunction "G_1") (pintype "passive"))
      (node (ref "R38") (pin "1") (pinfunction "1_1") (pintype "passive"))
    )
    (net (code "67") (name "Net-(Q10-D)") (class "Default")
      (node (ref "Q10") (pin "3") (pinfunction "D_3") (pintype "passive"))
      (node (ref "R42") (pin "2") (pinfunction "2_2") (pintype "passive"))
    )
    (net (code "68") (name "Net-(Q10-G)") (class "Default")
      (node (ref "Q10") (pin "1") (pinfunction "G_1") (pintype "passive"))
      (node (ref "R41") (pin "1") (pinfunction "1_1") (pintype "passive"))
    )
    (net (code "69") (name "Net-(Q11-D)") (class "Default")
      (node (ref "Q11") (pin "3") (pinfunction "D_3") (pintype "passive"))
      (node (ref "R45") (pin "2") (pinfunction "2_2") (pintype "passive"))
    )
    (net (code "70") (name "Net-(Q11-G)") (class "Default")
      (node (ref "Q11") (pin "1") (pinfunction "G_1") (pintype "passive"))
      (node (ref "R44") (pin "1") (pinfunction "1_1") (pintype "passive"))
    )
    (net (code "71") (name "Net-(Q12-D)") (class "Default")
      (node (ref "Q12") (pin "3") (pinfunction "D_3") (pintype "passive"))
      (node (ref "R48") (pin "2") (pinfunction "2_2") (pintype "passive"))
    )
    (net (code "72") (name "Net-(Q12-G)") (class "Default")
      (node (ref "Q12") (pin "1") (pinfunction "G_1") (pintype "passive"))
      (node (ref "R47") (pin "1") (pinfunction "1_1") (pintype "passive"))
    )
    (net (code "73") (name "Net-(TRANSFORMER-A-CX)") (class "Default")
      (node (ref "C18") (pin "1") (pinfunction "1_1") (pintype "passive"))
      (node (ref "TRANSFORMER-") (pin "10") (pinfunction "CX_10") (pintype "passive"))
    )
    (net (code "74") (name "Net-(TRANSFORMER-A-X+)") (class "Default")
      (node (ref "R49") (pin "1") (pinfunction "1_1") (pintype "passive"))
      (node (ref "TRANSFORMER-") (pin "11") (pinfunction "X+_11") (pintype "passive"))
      (node (ref "U$2") (pin "42") (pinfunction "SCK(IPA)_42") (pintype "bidirectional"))
    )
    (net (code "75") (name "Net-(TRANSFORMER-A-X-)") (class "Default")
      (node (ref "R49") (pin "2") (pinfunction "2_2") (pintype "passive"))
      (node (ref "TRANSFORMER-") (pin "9") (pinfunction "X-_9") (pintype "passive"))
      (node (ref "U$2") (pin "41") (pinfunction "CSB(IMA)_41") (pintype "bidirectional"))
    )
    (net (code "76") (name "Net-(TRANSFORMER-B-CX)") (class "Default")
      (node (ref "C17") (pin "1") (pinfunction "1_1") (pintype "passive"))
      (node (ref "TRANSFORMER-") (pin "15") (pinfunction "CX_15") (pintype "passive"))
    )
    (net (code "77") (name "Net-(TRANSFORMER-B-X+)") (class "Default")
      (node (ref "R1") (pin "1") (pinfunction "1_1") (pintype "passive"))
      (node (ref "TRANSFORMER-") (pin "16") (pinfunction "X+_16") (pintype "passive"))
      (node (ref "U$2") (pin "48") (pinfunction "IPB_48") (pintype "bidirectional"))
    )
    (net (code "78") (name "Net-(TRANSFORMER-B-X-)") (class "Default")
      (node (ref "R1") (pin "2") (pinfunction "2_2") (pintype "passive"))
      (node (ref "TRANSFORMER-") (pin "14") (pinfunction "X-_14") (pintype "passive"))
      (node (ref "U$2") (pin "47") (pinfunction "IMB_47") (pintype "bidirectional"))
    )
    (net (code "79") (name "Net-(U$2-IBIAS)") (class "Default")
      (node (ref "RB1") (pin "2") (pinfunction "2_2") (pintype "passive"))
      (node (ref "U$2") (pin "45") (pinfunction "IBIAS_45") (pintype "bidirectional"))
    )
    (net (code "80") (name "Net-(U$2-ICMP)") (class "Default")
      (node (ref "RB1") (pin "1") (pinfunction "1_1") (pintype "passive"))
      (node (ref "RB2") (pin "2") (pinfunction "2_2") (pintype "passive"))
      (node (ref "U$2") (pin "46") (pinfunction "ICMP_46") (pintype "bidirectional"))
    )
    (net (code "81") (name "unconnected-(TRANSFORMER-A-CD-Pad7)") (class "Default")
      (node (ref "TRANSFORMER-") (pin "7") (pinfunction "CD_7") (pintype "passive"))
    )
    (net (code "82") (name "unconnected-(TRANSFORMER-B-CD-Pad2)") (class "Default")
      (node (ref "TRANSFORMER-") (pin "2") (pinfunction "CD_2") (pintype "passive"))
    )
    (net (code "83") (name "unconnected-(U$2-GPI05-Pad33)") (class "Default")
      (node (ref "U$2") (pin "33") (pinfunction "GPI05_33") (pintype "bidirectional"))
    )
    (net (code "84") (name "unconnected-(U$2-S6-Pad15)") (class "Default")
      (node (ref "U$2") (pin "15") (pinfunction "S6_15") (pintype "bidirectional"))
    )
    (net (code "85") (name "unconnected-(U$2-S11-Pad5)") (class "Default")
      (node (ref "U$2") (pin "5") (pinfunction "S11_5") (pintype "bidirectional"))
    )
    (net (code "86") (name "unconnected-(U$2-S12-Pad3)") (class "Default")
      (node (ref "U$2") (pin "3") (pinfunction "S12_3") (pintype "bidirectional"))
    )
    (net (code "87") (name "unconnected-(U$2-WDT-Pad39)") (class "Default")
      (node (ref "U$2") (pin "39") (pinfunction "WDT_39") (pintype "bidirectional"))
    )
  )
)
